# TI_ESP_PCB2.net
KiCad netlist of a schematic drawn in EAGLE
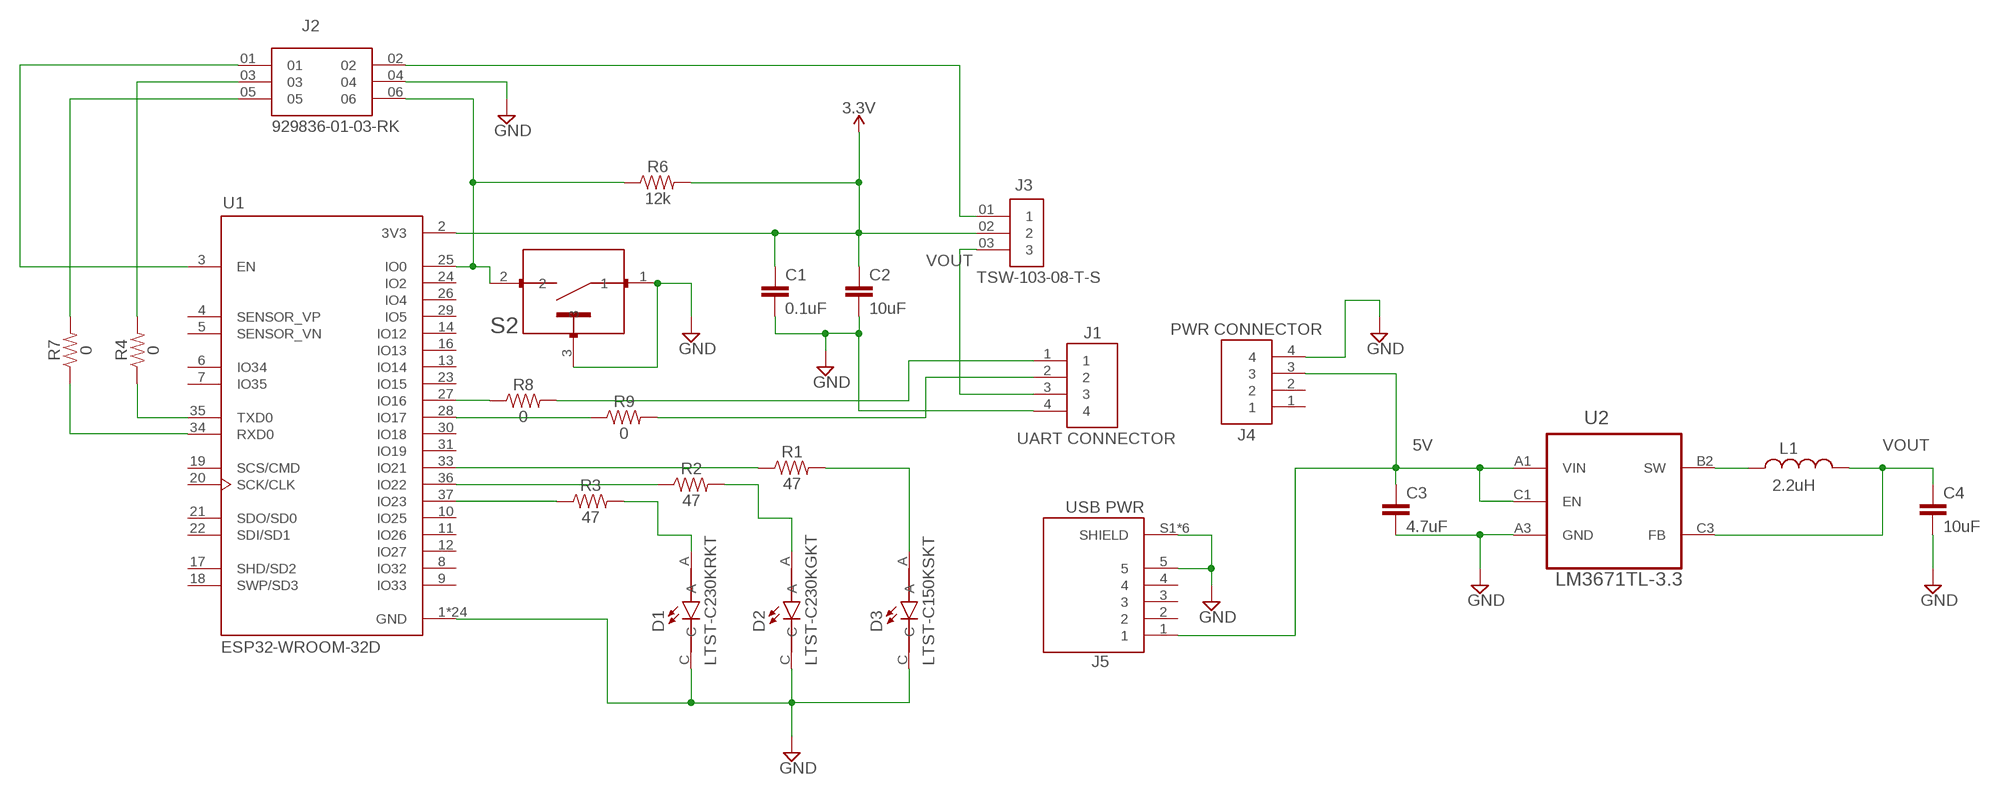
[diagram p0: schematic, sheet 1]

(export (version "E")
  (design (tool "Eeschema 10.0.6"))
  (components
    (comp (ref "C1")
      (value "0.1uF")
      (footprint "eagle-import:1206")
      (libsource (lib "eagle-import") (part "0.1UF-1206"))
    )
    (comp (ref "C2")
      (value "10uF")
      (footprint "eagle-import:1206")
      (libsource (lib "eagle-import") (part "10UF-1206"))
    )
    (comp (ref "C3")
      (value "4.7uF")
      (footprint "eagle-import:0805")
      (libsource (lib "eagle-import") (part "4.7UF"))
    )
    (comp (ref "C4")
      (value "10uF")
      (footprint "eagle-import:0805")
      (libsource (lib "eagle-import") (part "10UF"))
    )
    (comp (ref "D1")
      (value "LTST-C230KRKT")
      (footprint "eagle-import:LEDC3216X110")
      (fields (field (name "MF") "Lite-On Inc."))
      (libsource (lib "eagle-import") (part "LTST-C230KRKT"))
    )
    (comp (ref "D2")
      (value "LTST-C230KGKT")
      (footprint "eagle-import:LEDC3216X110")
      (fields (field (name "MF") "Lite-On Inc."))
      (libsource (lib "eagle-import") (part "LTST-C230KGKT"))
    )
    (comp (ref "D3")
      (value "LTST-C150KSKT")
      (footprint "eagle-import:LEDC3216X110")
      (fields (field (name "MF") "Lite-On Inc."))
      (libsource (lib "eagle-import") (part "LTST-C150KSKT"))
    )
    (comp (ref "J1")
      (value "UART CONNECTOR")
      (footprint "eagle-import:SEEED_114020163")
      (fields (field (name "MF") "Seeed Technology Co., Ltd") (field (name "MP") "110990030"))
      (libsource (lib "eagle-import") (part "4PIN_GROVE_CONNECTOR"))
    )
    (comp (ref "J2")
      (value "929836-01-03-RK")
      (footprint "eagle-import:3M-2X3_6PIN_CONNECTOR")
      (fields (field (name "MF") "3M"))
      (libsource (lib "eagle-import") (part "929836-01-03-RK"))
    )
    (comp (ref "J3")
      (value "TSW-103-08-T-S")
      (footprint "eagle-import:SAMTEC_TSW-103-08-T-S")
      (fields (field (name "MF") "Samtec Inc."))
      (libsource (lib "eagle-import") (part "TSW-103-08-T-S"))
    )
    (comp (ref "J4")
      (value "PWR CONNECTOR")
      (footprint "eagle-import:SEEED_114020163")
      (fields (field (name "MF") "Seeed Technology Co., Ltd") (field (name "MP") "110990030"))
      (libsource (lib "eagle-import") (part "4PIN_GROVE_CONNECTOR"))
    )
    (comp (ref "J5")
      (value "USB PWR")
      (footprint "eagle-import:AMPHENOL_10118194-0001LF")
      (fields (field (name "MF") "AMPHENOL ICC / FCI") (field (name "MP") "10118194-0001LF"))
      (libsource (lib "eagle-import") (part "10118194-0001LF"))
    )
    (comp (ref "L1")
      (value "2.2uH")
      (footprint "eagle-import:CDRH2D14NP-2R2NC")
      (libsource (lib "eagle-import") (part "CDRH2D14NP-2R2NC"))
    )
    (comp (ref "R1")
      (value "47")
      (footprint "eagle-import:1206")
      (libsource (lib "eagle-import") (part "47OHM"))
    )
    (comp (ref "R2")
      (value "47")
      (footprint "eagle-import:1206")
      (libsource (lib "eagle-import") (part "47OHM"))
    )
    (comp (ref "R3")
      (value "47")
      (footprint "eagle-import:1206")
      (libsource (lib "eagle-import") (part "47OHM"))
    )
    (comp (ref "R4")
      (value "0")
      (footprint "eagle-import:1206")
      (libsource (lib "eagle-import") (part "470OHM"))
    )
    (comp (ref "R6")
      (value "12k")
      (footprint "eagle-import:1206")
      (libsource (lib "eagle-import") (part "12KOHM"))
    )
    (comp (ref "R7")
      (value "0")
      (footprint "eagle-import:1206")
      (libsource (lib "eagle-import") (part "470OHM"))
    )
    (comp (ref "R8")
      (value "0")
      (footprint "eagle-import:1206")
      (libsource (lib "eagle-import") (part "470OHM"))
    )
    (comp (ref "R9")
      (value "0")
      (footprint "eagle-import:1206")
      (libsource (lib "eagle-import") (part "470OHM"))
    )
    (comp (ref "S2")
      (value "B3U-1100P")
      (footprint "eagle-import:SW_B3U-1100P")
      (fields (field (name "MF") "Omron"))
      (libsource (lib "eagle-import") (part "B3U-1100P"))
    )
    (comp (ref "U1")
      (value "ESP32-WROOM-32D")
      (footprint "eagle-import:MODULE_ESP32-WROOM-32D")
      (fields (field (name "MF") "Espressif Systems"))
      (libsource (lib "eagle-import") (part "ESP32-WROOM-32D"))
    )
    (comp (ref "U2")
      (value "LM3671TL-3.3")
      (footprint "eagle-import:BGA5C43PX50P3X2_105X138X60")
      (fields (field (name "MF") "Texas Instruments") (field (name "MP") "LM3671TL-3.3/NOPB"))
      (libsource (lib "eagle-import") (part "LM3671TL-3.3"))
    )
  )
  (nets
    (net (code "1") (name "/5V") (class "Default")
      (node (ref "C3") (pin "1") (pinfunction "1_1") (pintype "passive"))
      (node (ref "J4") (pin "3") (pinfunction "3_3") (pintype "passive"))
      (node (ref "J5") (pin "1") (pinfunction "1_1") (pintype "passive"))
      (node (ref "U2") (pin "A1") (pinfunction "VIN_A1") (pintype "input"))
      (node (ref "U2") (pin "C1") (pinfunction "EN_C1") (pintype "passive"))
    )
    (net (code "2") (name "/VOUT") (class "Default")
      (node (ref "C4") (pin "1") (pinfunction "1_1") (pintype "passive"))
      (node (ref "J1") (pin "3") (pinfunction "3_3") (pintype "passive"))
      (node (ref "J3") (pin "03") (pinfunction "3_03") (pintype "passive"))
      (node (ref "L1") (pin "2") (pinfunction "2_2") (pintype "passive"))
      (node (ref "U2") (pin "C3") (pinfunction "FB_C3") (pintype "passive"))
    )
    (net (code "3") (name "3.3V") (class "Default")
      (node (ref "C1") (pin "1") (pinfunction "1_1") (pintype "passive"))
      (node (ref "C2") (pin "1") (pinfunction "1_1") (pintype "passive"))
      (node (ref "J3") (pin "02") (pinfunction "2_02") (pintype "passive"))
      (node (ref "R6") (pin "2") (pinfunction "2_2") (pintype "passive"))
      (node (ref "U1") (pin "2") (pinfunction "3V3_2") (pintype "power_in"))
    )
    (net (code "4") (name "GND") (class "Default")
      (node (ref "C1") (pin "2") (pinfunction "2_2") (pintype "passive"))
      (node (ref "C2") (pin "2") (pinfunction "2_2") (pintype "passive"))
      (node (ref "C3") (pin "2") (pinfunction "2_2") (pintype "passive"))
      (node (ref "C4") (pin "2") (pinfunction "2_2") (pintype "passive"))
      (node (ref "D1") (pin "C") (pinfunction "C_C") (pintype "passive"))
      (node (ref "D2") (pin "C") (pinfunction "C_C") (pintype "passive"))
      (node (ref "D3") (pin "C") (pinfunction "C_C") (pintype "passive"))
      (node (ref "J1") (pin "4") (pinfunction "4_4") (pintype "passive"))
      (node (ref "J2") (pin "04") (pinfunction "04_04") (pintype "passive"))
      (node (ref "J4") (pin "4") (pinfunction "4_4") (pintype "passive"))
      (node (ref "J5") (pin "5") (pinfunction "5_5") (pintype "passive"))
      (node (ref "J5") (pin "S1") (pinfunction "SHIELD_S1") (pintype "passive"))
      (node (ref "J5") (pin "S2") (pinfunction "SHIELD_S2") (pintype "passive"))
      (node (ref "J5") (pin "S3") (pinfunction "SHIELD_S3") (pintype "passive"))
      (node (ref "J5") (pin "S4") (pinfunction "SHIELD_S4") (pintype "passive"))
      (node (ref "J5") (pin "S5") (pinfunction "SHIELD_S5") (pintype "passive"))
      (node (ref "J5") (pin "S6") (pinfunction "SHIELD_S6") (pintype "passive"))
      (node (ref "S2") (pin "1") (pinfunction "1_1") (pintype "passive"))
      (node (ref "S2") (pin "3") (pinfunction "3_3") (pintype "passive"))
      (node (ref "U1") (pin "1") (pinfunction "GND_1") (pintype "power_in"))
      (node (ref "U1") (pin "15") (pinfunction "GND_15") (pintype "power_in"))
      (node (ref "U1") (pin "38") (pinfunction "GND_38") (pintype "power_in"))
      (node (ref "U1") (pin "39_1") (pinfunction "GND_39_1") (pintype "power_in"))
      (node (ref "U1") (pin "39_10") (pinfunction "GND_39_10") (pintype "power_in"))
      (node (ref "U1") (pin "39_11") (pinfunction "GND_39_11") (pintype "power_in"))
      (node (ref "U1") (pin "39_12") (pinfunction "GND_39_12") (pintype "power_in"))
      (node (ref "U1") (pin "39_13") (pinfunction "GND_39_13") (pintype "power_in"))
      (node (ref "U1") (pin "39_14") (pinfunction "GND_39_14") (pintype "power_in"))
      (node (ref "U1") (pin "39_15") (pinfunction "GND_39_15") (pintype "power_in"))
      (node (ref "U1") (pin "39_16") (pinfunction "GND_39_16") (pintype "power_in"))
      (node (ref "U1") (pin "39_17") (pinfunction "GND_39_17") (pintype "power_in"))
      (node (ref "U1") (pin "39_18") (pinfunction "GND_39_18") (pintype "power_in"))
      (node (ref "U1") (pin "39_19") (pinfunction "GND_39_19") (pintype "power_in"))
      (node (ref "U1") (pin "39_2") (pinfunction "GND_39_2") (pintype "power_in"))
      (node (ref "U1") (pin "39_20") (pinfunction "GND_39_20") (pintype "power_in"))
      (node (ref "U1") (pin "39_21") (pinfunction "GND_39_21") (pintype "power_in"))
      (node (ref "U1") (pin "39_3") (pinfunction "GND_39_3") (pintype "power_in"))
      (node (ref "U1") (pin "39_4") (pinfunction "GND_39_4") (pintype "power_in"))
      (node (ref "U1") (pin "39_5") (pinfunction "GND_39_5") (pintype "power_in"))
      (node (ref "U1") (pin "39_6") (pinfunction "GND_39_6") (pintype "power_in"))
      (node (ref "U1") (pin "39_7") (pinfunction "GND_39_7") (pintype "power_in"))
      (node (ref "U1") (pin "39_8") (pinfunction "GND_39_8") (pintype "power_in"))
      (node (ref "U1") (pin "39_9") (pinfunction "GND_39_9") (pintype "power_in"))
      (node (ref "U2") (pin "A3") (pinfunction "GND_A3") (pintype "passive"))
    )
    (net (code "5") (name "Net-(D1-PadA)") (class "Default")
      (node (ref "D1") (pin "A") (pinfunction "A_A") (pintype "passive"))
      (node (ref "R3") (pin "2") (pinfunction "2_2") (pintype "passive"))
    )
    (net (code "6") (name "Net-(D2-PadA)") (class "Default")
      (node (ref "D2") (pin "A") (pinfunction "A_A") (pintype "passive"))
      (node (ref "R2") (pin "2") (pinfunction "2_2") (pintype "passive"))
    )
    (net (code "7") (name "Net-(D3-PadA)") (class "Default")
      (node (ref "D3") (pin "A") (pinfunction "A_A") (pintype "passive"))
      (node (ref "R1") (pin "2") (pinfunction "2_2") (pintype "passive"))
    )
    (net (code "8") (name "Net-(J1-Pad1)") (class "Default")
      (node (ref "J1") (pin "1") (pinfunction "1_1") (pintype "passive"))
      (node (ref "R8") (pin "2") (pinfunction "2_2") (pintype "passive"))
    )
    (net (code "9") (name "Net-(J1-Pad2)") (class "Default")
      (node (ref "J1") (pin "2") (pinfunction "2_2") (pintype "passive"))
      (node (ref "R9") (pin "2") (pinfunction "2_2") (pintype "passive"))
    )
    (net (code "10") (name "Net-(J2-Pad03)") (class "Default")
      (node (ref "J2") (pin "03") (pinfunction "03_03") (pintype "passive"))
      (node (ref "R4") (pin "2") (pinfunction "2_2") (pintype "passive"))
    )
    (net (code "11") (name "Net-(J2-Pad05)") (class "Default")
      (node (ref "J2") (pin "05") (pinfunction "05_05") (pintype "passive"))
      (node (ref "R7") (pin "2") (pinfunction "2_2") (pintype "passive"))
    )
    (net (code "12") (name "Net-(J3-1)") (class "Default")
      (node (ref "J2") (pin "02") (pinfunction "02_02") (pintype "passive"))
      (node (ref "J3") (pin "01") (pinfunction "1_01") (pintype "passive"))
    )
    (net (code "13") (name "Net-(U1-EN)") (class "Default")
      (node (ref "J2") (pin "01") (pinfunction "01_01") (pintype "passive"))
      (node (ref "U1") (pin "3") (pinfunction "EN_3") (pintype "input"))
    )
    (net (code "14") (name "Net-(U1-IO0)") (class "Default")
      (node (ref "J2") (pin "06") (pinfunction "06_06") (pintype "passive"))
      (node (ref "R6") (pin "1") (pinfunction "1_1") (pintype "passive"))
      (node (ref "S2") (pin "2") (pinfunction "2_2") (pintype "passive"))
      (node (ref "U1") (pin "25") (pinfunction "IO0_25") (pintype "bidirectional"))
    )
    (net (code "15") (name "Net-(U1-IO16)") (class "Default")
      (node (ref "R8") (pin "1") (pinfunction "1_1") (pintype "passive"))
      (node (ref "U1") (pin "27") (pinfunction "IO16_27") (pintype "bidirectional"))
    )
    (net (code "16") (name "Net-(U1-IO17)") (class "Default")
      (node (ref "R9") (pin "1") (pinfunction "1_1") (pintype "passive"))
      (node (ref "U1") (pin "28") (pinfunction "IO17_28") (pintype "bidirectional"))
    )
    (net (code "17") (name "Net-(U1-IO21)") (class "Default")
      (node (ref "R1") (pin "1") (pinfunction "1_1") (pintype "passive"))
      (node (ref "U1") (pin "33") (pinfunction "IO21_33") (pintype "bidirectional"))
    )
    (net (code "18") (name "Net-(U1-IO22)") (class "Default")
      (node (ref "R2") (pin "1") (pinfunction "1_1") (pintype "passive"))
      (node (ref "U1") (pin "36") (pinfunction "IO22_36") (pintype "bidirectional"))
    )
    (net (code "19") (name "Net-(U1-IO23)") (class "Default")
      (node (ref "R3") (pin "1") (pinfunction "1_1") (pintype "passive"))
      (node (ref "U1") (pin "37") (pinfunction "IO23_37") (pintype "bidirectional"))
    )
    (net (code "20") (name "Net-(U1-RXD0)") (class "Default")
      (node (ref "R7") (pin "1") (pinfunction "1_1") (pintype "passive"))
      (node (ref "U1") (pin "34") (pinfunction "RXD0_34") (pintype "bidirectional"))
    )
    (net (code "21") (name "Net-(U1-TXD0)") (class "Default")
      (node (ref "R4") (pin "1") (pinfunction "1_1") (pintype "passive"))
      (node (ref "U1") (pin "35") (pinfunction "TXD0_35") (pintype "bidirectional"))
    )
    (net (code "22") (name "Net-(U2-SW)") (class "Default")
      (node (ref "L1") (pin "1") (pinfunction "1_1") (pintype "passive"))
      (node (ref "U2") (pin "B2") (pinfunction "SW_B2") (pintype "passive"))
    )
    (net (code "23") (name "unconnected-(J4-Pad1)") (class "Default")
      (node (ref "J4") (pin "1") (pinfunction "1_1") (pintype "passive"))
    )
    (net (code "24") (name "unconnected-(J4-Pad2)") (class "Default")
      (node (ref "J4") (pin "2") (pinfunction "2_2") (pintype "passive"))
    )
    (net (code "25") (name "unconnected-(J5-Pad2)") (class "Default")
      (node (ref "J5") (pin "2") (pinfunction "2_2") (pintype "passive"))
    )
    (net (code "26") (name "unconnected-(J5-Pad3)") (class "Default")
      (node (ref "J5") (pin "3") (pinfunction "3_3") (pintype "passive"))
    )
    (net (code "27") (name "unconnected-(J5-Pad4)") (class "Default")
      (node (ref "J5") (pin "4") (pinfunction "4_4") (pintype "passive"))
    )
    (net (code "28") (name "unconnected-(U1-IO2-Pad24)") (class "Default")
      (node (ref "U1") (pin "24") (pinfunction "IO2_24") (pintype "bidirectional"))
    )
    (net (code "29") (name "unconnected-(U1-IO4-Pad26)") (class "Default")
      (node (ref "U1") (pin "26") (pinfunction "IO4_26") (pintype "bidirectional"))
    )
    (net (code "30") (name "unconnected-(U1-IO5-Pad29)") (class "Default")
      (node (ref "U1") (pin "29") (pinfunction "IO5_29") (pintype "bidirectional"))
    )
    (net (code "31") (name "unconnected-(U1-IO12-Pad14)") (class "Default")
      (node (ref "U1") (pin "14") (pinfunction "IO12_14") (pintype "bidirectional"))
    )
    (net (code "32") (name "unconnected-(U1-IO13-Pad16)") (class "Default")
      (node (ref "U1") (pin "16") (pinfunction "IO13_16") (pintype "bidirectional"))
    )
    (net (code "33") (name "unconnected-(U1-IO14-Pad13)") (class "Default")
      (node (ref "U1") (pin "13") (pinfunction "IO14_13") (pintype "bidirectional"))
    )
    (net (code "34") (name "unconnected-(U1-IO15-Pad23)") (class "Default")
      (node (ref "U1") (pin "23") (pinfunction "IO15_23") (pintype "bidirectional"))
    )
    (net (code "35") (name "unconnected-(U1-IO18-Pad30)") (class "Default")
      (node (ref "U1") (pin "30") (pinfunction "IO18_30") (pintype "bidirectional"))
    )
    (net (code "36") (name "unconnected-(U1-IO19-Pad31)") (class "Default")
      (node (ref "U1") (pin "31") (pinfunction "IO19_31") (pintype "bidirectional"))
    )
    (net (code "37") (name "unconnected-(U1-IO25-Pad10)") (class "Default")
      (node (ref "U1") (pin "10") (pinfunction "IO25_10") (pintype "bidirectional"))
    )
    (net (code "38") (name "unconnected-(U1-IO26-Pad11)") (class "Default")
      (node (ref "U1") (pin "11") (pinfunction "IO26_11") (pintype "bidirectional"))
    )
    (net (code "39") (name "unconnected-(U1-IO27-Pad12)") (class "Default")
      (node (ref "U1") (pin "12") (pinfunction "IO27_12") (pintype "bidirectional"))
    )
    (net (code "40") (name "unconnected-(U1-IO32-Pad8)") (class "Default")
      (node (ref "U1") (pin "8") (pinfunction "IO32_8") (pintype "bidirectional"))
    )
    (net (code "41") (name "unconnected-(U1-IO33-Pad9)") (class "Default")
      (node (ref "U1") (pin "9") (pinfunction "IO33_9") (pintype "bidirectional"))
    )
    (net (code "42") (name "unconnected-(U1-IO34-Pad6)") (class "Default")
      (node (ref "U1") (pin "6") (pinfunction "IO34_6") (pintype "input"))
    )
    (net (code "43") (name "unconnected-(U1-IO35-Pad7)") (class "Default")
      (node (ref "U1") (pin "7") (pinfunction "IO35_7") (pintype "input"))
    )
    (net (code "44") (name "unconnected-(U1-SCK{slash}CLK-Pad20)") (class "Default")
      (node (ref "U1") (pin "20") (pinfunction "SCK/CLK_20") (pintype "bidirectional"))
    )
    (net (code "45") (name "unconnected-(U1-SCS{slash}CMD-Pad19)") (class "Default")
      (node (ref "U1") (pin "19") (pinfunction "SCS/CMD_19") (pintype "bidirectional"))
    )
    (net (code "46") (name "unconnected-(U1-SDI{slash}SD1-Pad22)") (class "Default")
      (node (ref "U1") (pin "22") (pinfunction "SDI/SD1_22") (pintype "bidirectional"))
    )
    (net (code "47") (name "unconnected-(U1-SDO{slash}SD0-Pad21)") (class "Default")
      (node (ref "U1") (pin "21") (pinfunction "SDO/SD0_21") (pintype "bidirectional"))
    )
    (net (code "48") (name "unconnected-(U1-SENSOR_VN-Pad5)") (class "Default")
      (node (ref "U1") (pin "5") (pinfunction "SENSOR_VN_5") (pintype "input"))
    )
    (net (code "49") (name "unconnected-(U1-SENSOR_VP-Pad4)") (class "Default")
      (node (ref "U1") (pin "4") (pinfunction "SENSOR_VP_4") (pintype "input"))
    )
    (net (code "50") (name "unconnected-(U1-SHD{slash}SD2-Pad17)") (class "Default")
      (node (ref "U1") (pin "17") (pinfunction "SHD/SD2_17") (pintype "bidirectional"))
    )
    (net (code "51") (name "unconnected-(U1-SWP{slash}SD3-Pad18)") (class "Default")
      (node (ref "U1") (pin "18") (pinfunction "SWP/SD3_18") (pintype "bidirectional"))
    )
  )
)
